# L298N.net
KiCad netlist of a schematic drawn in Altium Designer
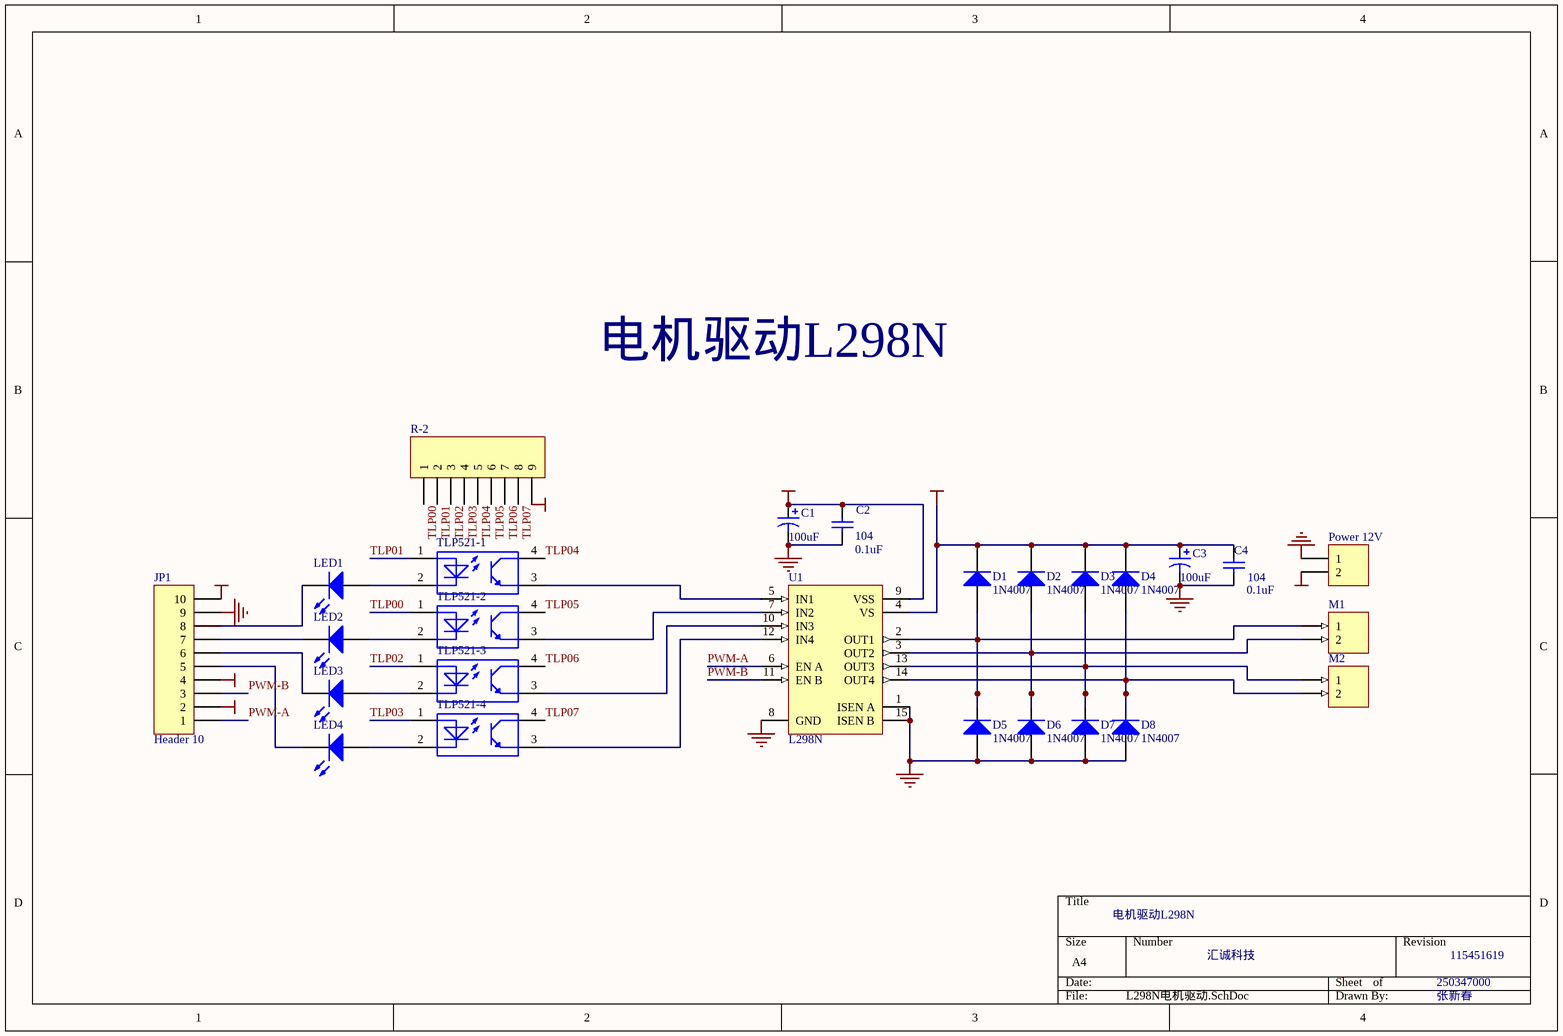
[diagram p0: L298N电机驱动.SchDoc]

(export (version "E")
  (design (tool "Eeschema 10.0.6"))
  (components
    (comp (ref "C1")
      (value "100uF")
      (footprint "CAPPR2-5x6.8")
      (description "Polarized Capacitor (Surface Mount)")
      (fields (field (name "PUBLISHER") "Altium Limited"))
      (libsource (lib "Miscellaneous Devices") (part "Cap Pol3"))
    )
    (comp (ref "C2")
      (value "104")
      (footprint "BAT-2")
      (description "Capacitor")
      (fields (field (name "ALTIUM_VALUE") "0.1uF") (field (name "PUBLISHER") "Altium Limited"))
      (libsource (lib "Miscellaneous Devices") (part "Cap"))
    )
    (comp (ref "C3")
      (value "100uF")
      (footprint "CAPPR2-5x6.8")
      (description "Polarized Capacitor (Surface Mount)")
      (fields (field (name "PUBLISHER") "Altium Limited"))
      (libsource (lib "Miscellaneous Devices") (part "Cap Pol3"))
    )
    (comp (ref "C4")
      (value "104")
      (footprint "BAT-2")
      (description "Capacitor")
      (fields (field (name "ALTIUM_VALUE") "0.1uF") (field (name "PUBLISHER") "Altium Limited"))
      (libsource (lib "Miscellaneous Devices") (part "Cap"))
    )
    (comp (ref "D1")
      (value "1N4007")
      (footprint "DIO7.8-4.6x2")
      (description "1 Amp General Purpose Rectifier")
      (fields (field (name "PUBLISHER") "Altium Limited"))
      (libsource (lib "Miscellaneous Devices") (part "Diode 1N4007"))
    )
    (comp (ref "D2")
      (value "1N4007")
      (footprint "DIO7.8-4.6x2")
      (description "1 Amp General Purpose Rectifier")
      (fields (field (name "PUBLISHER") "Altium Limited"))
      (libsource (lib "Miscellaneous Devices") (part "Diode 1N4007"))
    )
    (comp (ref "D3")
      (value "1N4007")
      (footprint "DIO7.8-4.6x2")
      (description "1 Amp General Purpose Rectifier")
      (fields (field (name "PUBLISHER") "Altium Limited"))
      (libsource (lib "Miscellaneous Devices") (part "Diode 1N4007"))
    )
    (comp (ref "D4")
      (value "1N4007")
      (footprint "DIO7.8-4.6x2")
      (description "1 Amp General Purpose Rectifier")
      (fields (field (name "PUBLISHER") "Altium Limited"))
      (libsource (lib "Miscellaneous Devices") (part "Diode 1N4007"))
    )
    (comp (ref "D5")
      (value "1N4007")
      (footprint "DIO7.8-4.6x2")
      (description "1 Amp General Purpose Rectifier")
      (fields (field (name "PUBLISHER") "Altium Limited"))
      (libsource (lib "Miscellaneous Devices") (part "Diode 1N4007"))
    )
    (comp (ref "D6")
      (value "1N4007")
      (footprint "DIO7.8-4.6x2")
      (description "1 Amp General Purpose Rectifier")
      (fields (field (name "PUBLISHER") "Altium Limited"))
      (libsource (lib "Miscellaneous Devices") (part "Diode 1N4007"))
    )
    (comp (ref "D7")
      (value "1N4007")
      (footprint "DIO7.8-4.6x2")
      (description "1 Amp General Purpose Rectifier")
      (fields (field (name "PUBLISHER") "Altium Limited"))
      (libsource (lib "Miscellaneous Devices") (part "Diode 1N4007"))
    )
    (comp (ref "D8")
      (value "1N4007")
      (footprint "DIO7.8-4.6x2")
      (description "1 Amp General Purpose Rectifier")
      (fields (field (name "PUBLISHER") "Altium Limited"))
      (libsource (lib "Miscellaneous Devices") (part "Diode 1N4007"))
    )
    (comp (ref "JP1")
      (value "Header 10")
      (footprint "HDR1X10")
      (description "Header, 10-Pin")
      (fields (field (name "PUBLISHER") "Altium Limited"))
      (libsource (lib "Miscellaneous Connectors") (part "Header 10"))
    )
    (comp (ref "LED1")
      (value "~")
      (footprint "HDR1X2")
      (description "Typical BLUE SiC LED")
      (fields (field (name "PUBLISHER") "Altium Limited"))
      (libsource (lib "Miscellaneous Devices") (part "LED3"))
    )
    (comp (ref "LED2")
      (value "~")
      (footprint "HDR1X2")
      (description "Typical BLUE SiC LED")
      (fields (field (name "PUBLISHER") "Altium Limited"))
      (libsource (lib "Miscellaneous Devices") (part "LED3"))
    )
    (comp (ref "LED3")
      (value "~")
      (footprint "HDR1X2")
      (description "Typical BLUE SiC LED")
      (fields (field (name "PUBLISHER") "Altium Limited"))
      (libsource (lib "Miscellaneous Devices") (part "LED3"))
    )
    (comp (ref "LED4")
      (value "~")
      (footprint "HDR1X2")
      (description "Typical BLUE SiC LED")
      (fields (field (name "PUBLISHER") "Altium Limited"))
      (libsource (lib "Miscellaneous Devices") (part "LED3"))
    )
    (comp (ref "M1")
      (value "~")
      (footprint "JK128")
      (description "Header, 2-Pin")
      (fields (field (name "PUBLISHER") "Altium Limited"))
      (libsource (lib "Miscellaneous Connectors") (part "MHDR1X2"))
    )
    (comp (ref "M2")
      (value "~")
      (footprint "JK128")
      (description "Header, 2-Pin")
      (fields (field (name "PUBLISHER") "Altium Limited"))
      (libsource (lib "Miscellaneous Connectors") (part "MHDR1X2"))
    )
    (comp (ref "Power 12V")
      (value "~")
      (footprint "JK128")
      (description "Header, 2-Pin")
      (fields (field (name "PUBLISHER") "Altium Limited"))
      (libsource (lib "Miscellaneous Connectors") (part "MHDR1X2"))
    )
    (comp (ref "R-2")
      (value "~")
      (footprint "HDR1X9")
      (description "Header, 9-Pin")
      (fields (field (name "PUBLISHER") "Altium Limited"))
      (libsource (lib "Miscellaneous Connectors") (part "Header 9"))
    )
    (comp (ref "TLP521-1") (value "~") (footprint "DIP4") (libsource (lib "MyInt_Lib") (part "TLP521-1")))
    (comp (ref "TLP521-2") (value "~") (footprint "DIP4") (libsource (lib "MyInt_Lib") (part "TLP521-1")))
    (comp (ref "TLP521-3") (value "~") (footprint "DIP4") (libsource (lib "MyInt_Lib") (part "TLP521-1")))
    (comp (ref "TLP521-4") (value "~") (footprint "DIP4") (libsource (lib "MyInt_Lib") (part "TLP521-1")))
    (comp (ref "U1")
      (value "L298N")
      (footprint "DFM-T15/X1.6V")
      (description "Dual Full Bridge Driver")
      (fields (field (name "PUBLISHER") "Altium Limited"))
      (libsource (lib "ST Interface DC Motor Controller") (part "L298N"))
    )
  )
  (nets
    (net (code "1") (name "+5V") (class "Default")
      (node (ref "C1") (pin "1") (pinfunction "1_1") (pintype "passive"))
      (node (ref "C2") (pin "2") (pinfunction "2_2") (pintype "passive"))
      (node (ref "JP1") (pin "10") (pinfunction "10_10") (pintype "passive"))
      (node (ref "JP1") (pin "2") (pinfunction "2_2") (pintype "passive"))
      (node (ref "JP1") (pin "4") (pinfunction "4_4") (pintype "passive"))
      (node (ref "R-2") (pin "9") (pinfunction "9_9") (pintype "passive"))
      (node (ref "U1") (pin "9") (pinfunction "VSS_9") (pintype "power_in"))
    )
    (net (code "2") (name "+12V") (class "Default")
      (node (ref "C3") (pin "1") (pinfunction "1_1") (pintype "passive"))
      (node (ref "C4") (pin "2") (pinfunction "2_2") (pintype "passive"))
      (node (ref "D1") (pin "2") (pinfunction "K_2") (pintype "passive"))
      (node (ref "D2") (pin "2") (pinfunction "K_2") (pintype "passive"))
      (node (ref "D3") (pin "2") (pinfunction "K_2") (pintype "passive"))
      (node (ref "D4") (pin "2") (pinfunction "K_2") (pintype "passive"))
      (node (ref "Power 12V") (pin "2") (pinfunction "2_2") (pintype "power_in"))
      (node (ref "U1") (pin "4") (pinfunction "VS_4") (pintype "power_in"))
    )
    (net (code "3") (name "/PWM-A") (class "Default")
      (node (ref "JP1") (pin "1") (pinfunction "1_1") (pintype "passive"))
      (node (ref "U1") (pin "6") (pinfunction "EN_A_6") (pintype "input"))
    )
    (net (code "4") (name "/PWM-B") (class "Default")
      (node (ref "JP1") (pin "3") (pinfunction "3_3") (pintype "passive"))
      (node (ref "U1") (pin "11") (pinfunction "EN_B_11") (pintype "input"))
    )
    (net (code "5") (name "/TLP00") (class "Default")
      (node (ref "R-2") (pin "1") (pinfunction "1_1") (pintype "passive"))
      (node (ref "TLP521-2") (pin "1") (pinfunction "1_1") (pintype "passive"))
    )
    (net (code "6") (name "/TLP01") (class "Default")
      (node (ref "R-2") (pin "2") (pinfunction "2_2") (pintype "passive"))
      (node (ref "TLP521-1") (pin "1") (pinfunction "1_1") (pintype "passive"))
    )
    (net (code "7") (name "/TLP02") (class "Default")
      (node (ref "R-2") (pin "3") (pinfunction "3_3") (pintype "passive"))
      (node (ref "TLP521-3") (pin "1") (pinfunction "1_1") (pintype "passive"))
    )
    (net (code "8") (name "/TLP03") (class "Default")
      (node (ref "R-2") (pin "4") (pinfunction "4_4") (pintype "passive"))
      (node (ref "TLP521-4") (pin "1") (pinfunction "1_1") (pintype "passive"))
    )
    (net (code "9") (name "/TLP04") (class "Default")
      (node (ref "R-2") (pin "5") (pinfunction "5_5") (pintype "passive"))
      (node (ref "TLP521-1") (pin "4") (pinfunction "4_4") (pintype "passive"))
    )
    (net (code "10") (name "/TLP05") (class "Default")
      (node (ref "R-2") (pin "6") (pinfunction "6_6") (pintype "passive"))
      (node (ref "TLP521-2") (pin "4") (pinfunction "4_4") (pintype "passive"))
    )
    (net (code "11") (name "/TLP06") (class "Default")
      (node (ref "R-2") (pin "7") (pinfunction "7_7") (pintype "passive"))
      (node (ref "TLP521-3") (pin "4") (pinfunction "4_4") (pintype "passive"))
    )
    (net (code "12") (name "/TLP07") (class "Default")
      (node (ref "R-2") (pin "8") (pinfunction "8_8") (pintype "passive"))
      (node (ref "TLP521-4") (pin "4") (pinfunction "4_4") (pintype "passive"))
    )
    (net (code "13") (name "GND") (class "Default")
      (node (ref "C1") (pin "2") (pinfunction "2_2") (pintype "passive"))
      (node (ref "C2") (pin "1") (pinfunction "1_1") (pintype "passive"))
      (node (ref "JP1") (pin "9") (pinfunction "9_9") (pintype "passive"))
      (node (ref "U1") (pin "8") (pinfunction "GND_8") (pintype "power_in"))
    )
    (net (code "14") (name "GND-12") (class "Default")
      (node (ref "C3") (pin "2") (pinfunction "2_2") (pintype "passive"))
      (node (ref "C4") (pin "1") (pinfunction "1_1") (pintype "passive"))
      (node (ref "D5") (pin "1") (pinfunction "A_1") (pintype "passive"))
      (node (ref "D6") (pin "1") (pinfunction "A_1") (pintype "passive"))
      (node (ref "D7") (pin "1") (pinfunction "A_1") (pintype "passive"))
      (node (ref "D8") (pin "1") (pinfunction "A_1") (pintype "passive"))
      (node (ref "Power 12V") (pin "1") (pinfunction "1_1") (pintype "power_in"))
      (node (ref "U1") (pin "1") (pinfunction "ISEN_A_1") (pintype "passive"))
      (node (ref "U1") (pin "15") (pinfunction "ISEN_B_15") (pintype "passive"))
    )
    (net (code "15") (name "Net-(D1-A)") (class "Default")
      (node (ref "D1") (pin "1") (pinfunction "A_1") (pintype "passive"))
      (node (ref "D5") (pin "2") (pinfunction "K_2") (pintype "passive"))
      (node (ref "M1") (pin "1") (pinfunction "1_1") (pintype "power_in"))
      (node (ref "U1") (pin "2") (pinfunction "OUT1_2") (pintype "output"))
    )
    (net (code "16") (name "Net-(D2-A)") (class "Default")
      (node (ref "D2") (pin "1") (pinfunction "A_1") (pintype "passive"))
      (node (ref "D6") (pin "2") (pinfunction "K_2") (pintype "passive"))
      (node (ref "M1") (pin "2") (pinfunction "2_2") (pintype "power_in"))
      (node (ref "U1") (pin "3") (pinfunction "OUT2_3") (pintype "output"))
    )
    (net (code "17") (name "Net-(D3-A)") (class "Default")
      (node (ref "D3") (pin "1") (pinfunction "A_1") (pintype "passive"))
      (node (ref "D7") (pin "2") (pinfunction "K_2") (pintype "passive"))
      (node (ref "M2") (pin "1") (pinfunction "1_1") (pintype "power_in"))
      (node (ref "U1") (pin "13") (pinfunction "OUT3_13") (pintype "output"))
    )
    (net (code "18") (name "Net-(D4-A)") (class "Default")
      (node (ref "D4") (pin "1") (pinfunction "A_1") (pintype "passive"))
      (node (ref "D8") (pin "2") (pinfunction "K_2") (pintype "passive"))
      (node (ref "M2") (pin "2") (pinfunction "2_2") (pintype "power_in"))
      (node (ref "U1") (pin "14") (pinfunction "OUT4_14") (pintype "output"))
    )
    (net (code "19") (name "Net-(LED1-A)") (class "Default")
      (node (ref "LED1") (pin "1") (pinfunction "A_1") (pintype "passive"))
      (node (ref "TLP521-1") (pin "2") (pinfunction "2_2") (pintype "passive"))
    )
    (net (code "20") (name "Net-(LED1-K)") (class "Default")
      (node (ref "JP1") (pin "8") (pinfunction "8_8") (pintype "passive"))
      (node (ref "LED1") (pin "2") (pinfunction "K_2") (pintype "passive"))
    )
    (net (code "21") (name "Net-(LED2-A)") (class "Default")
      (node (ref "LED2") (pin "1") (pinfunction "A_1") (pintype "passive"))
      (node (ref "TLP521-2") (pin "2") (pinfunction "2_2") (pintype "passive"))
    )
    (net (code "22") (name "Net-(LED2-K)") (class "Default")
      (node (ref "JP1") (pin "7") (pinfunction "7_7") (pintype "passive"))
      (node (ref "LED2") (pin "2") (pinfunction "K_2") (pintype "passive"))
    )
    (net (code "23") (name "Net-(LED3-A)") (class "Default")
      (node (ref "LED3") (pin "1") (pinfunction "A_1") (pintype "passive"))
      (node (ref "TLP521-3") (pin "2") (pinfunction "2_2") (pintype "passive"))
    )
    (net (code "24") (name "Net-(LED3-K)") (class "Default")
      (node (ref "JP1") (pin "6") (pinfunction "6_6") (pintype "passive"))
      (node (ref "LED3") (pin "2") (pinfunction "K_2") (pintype "passive"))
    )
    (net (code "25") (name "Net-(LED4-A)") (class "Default")
      (node (ref "LED4") (pin "1") (pinfunction "A_1") (pintype "passive"))
      (node (ref "TLP521-4") (pin "2") (pinfunction "2_2") (pintype "passive"))
    )
    (net (code "26") (name "Net-(LED4-K)") (class "Default")
      (node (ref "JP1") (pin "5") (pinfunction "5_5") (pintype "passive"))
      (node (ref "LED4") (pin "2") (pinfunction "K_2") (pintype "passive"))
    )
    (net (code "27") (name "Net-(U1-IN1)") (class "Default")
      (node (ref "TLP521-1") (pin "3") (pinfunction "3_3") (pintype "passive"))
      (node (ref "U1") (pin "5") (pinfunction "IN1_5") (pintype "input"))
    )
    (net (code "28") (name "Net-(U1-IN2)") (class "Default")
      (node (ref "TLP521-2") (pin "3") (pinfunction "3_3") (pintype "passive"))
      (node (ref "U1") (pin "7") (pinfunction "IN2_7") (pintype "input"))
    )
    (net (code "29") (name "Net-(U1-IN3)") (class "Default")
      (node (ref "TLP521-3") (pin "3") (pinfunction "3_3") (pintype "passive"))
      (node (ref "U1") (pin "10") (pinfunction "IN3_10") (pintype "input"))
    )
    (net (code "30") (name "Net-(U1-IN4)") (class "Default")
      (node (ref "TLP521-4") (pin "3") (pinfunction "3_3") (pintype "passive"))
      (node (ref "U1") (pin "12") (pinfunction "IN4_12") (pintype "input"))
    )
  )
)
